# SWAPv0_1.net
KiCad netlist of a schematic drawn in EAGLE
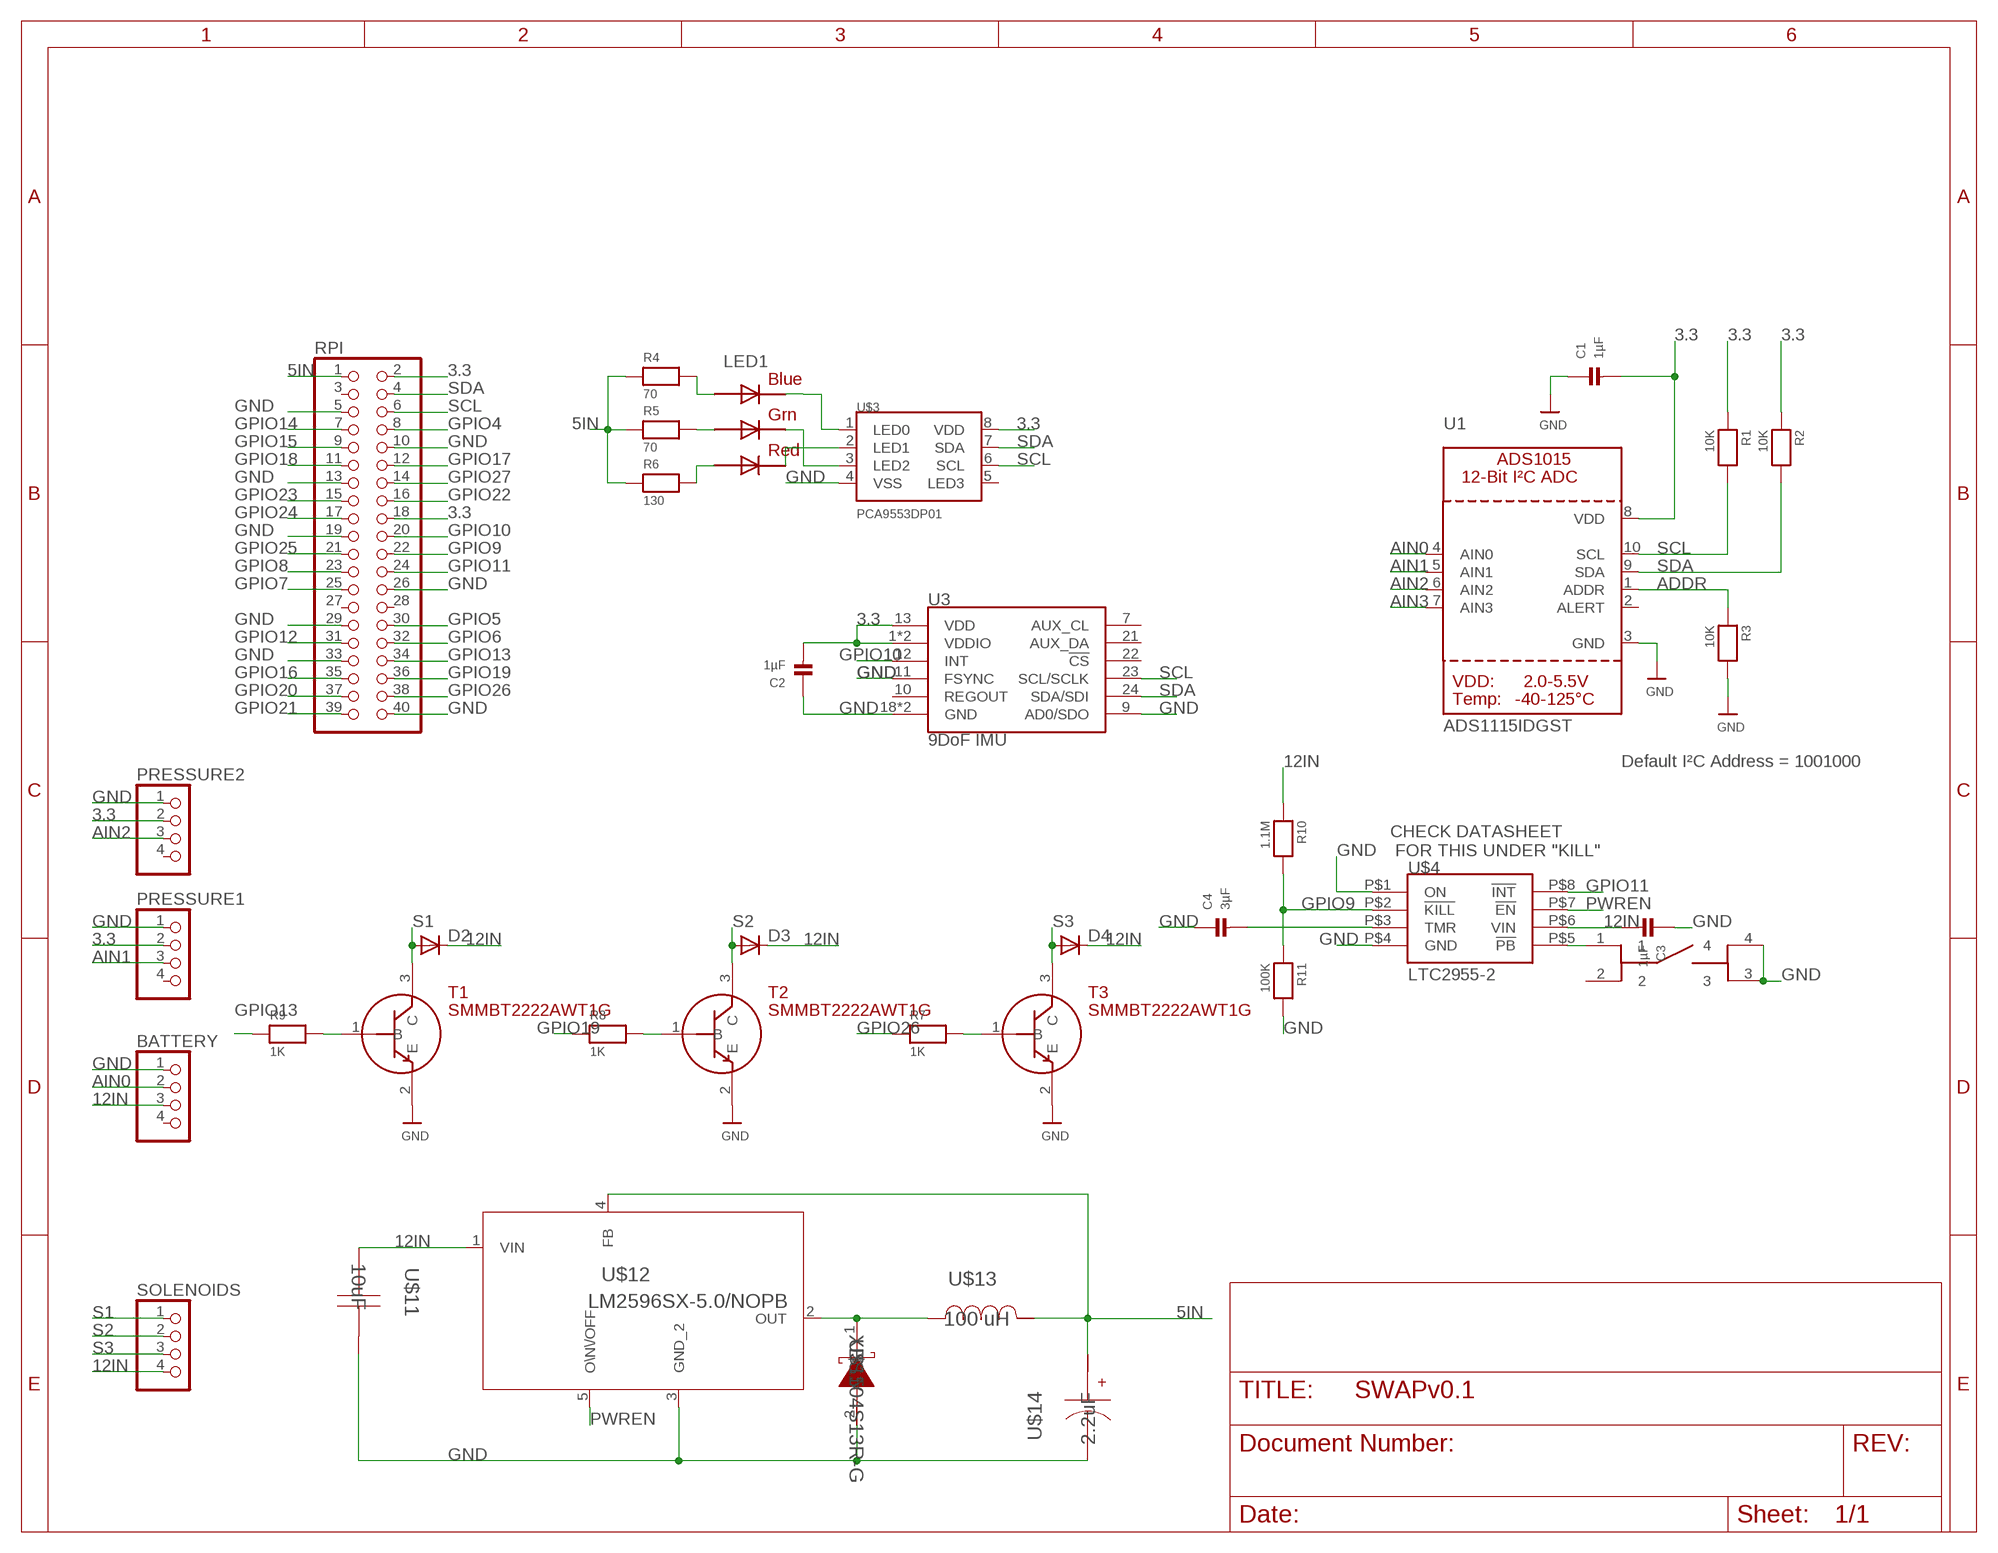
[diagram p0: schematic, sheet 1]

(export (version "E")
  (design (tool "Eeschema 10.0.6"))
  (components
    (comp (ref "BATTERY")
      (value "JST_4PIN")
      (footprint "eagle-import:JSTPH4")
      (libsource (lib "eagle-import") (part "JST_4PIN"))
    )
    (comp (ref "C1")
      (value "1µF")
      (footprint "eagle-import:1206")
      (libsource (lib "eagle-import") (part "CAP_CERAMIC1206"))
    )
    (comp (ref "C2")
      (value "1µF")
      (footprint "eagle-import:1206")
      (libsource (lib "eagle-import") (part "CAP_CERAMIC1206"))
    )
    (comp (ref "C3")
      (value "1µF")
      (footprint "eagle-import:1206")
      (libsource (lib "eagle-import") (part "CAP_CERAMIC1206"))
    )
    (comp (ref "C4")
      (value "3µF")
      (footprint "eagle-import:1206")
      (libsource (lib "eagle-import") (part "CAP_CERAMIC1206"))
    )
    (comp (ref "D2")
      (value "DIODE-DO214AA")
      (footprint "eagle-import:DO214AA")
      (libsource (lib "eagle-import") (part "DIODE-DO214AA"))
    )
    (comp (ref "D3")
      (value "DIODE-DO214AA")
      (footprint "eagle-import:DO214AA")
      (libsource (lib "eagle-import") (part "DIODE-DO214AA"))
    )
    (comp (ref "D4")
      (value "DIODE-DO214AA")
      (footprint "eagle-import:DO214AA")
      (libsource (lib "eagle-import") (part "DIODE-DO214AA"))
    )
    (comp (ref "LED1")
      (value "RGBLED5050")
      (footprint "eagle-import:RGBLED5050")
      (libsource (lib "eagle-import") (part "RGBLED5050"))
    )
    (comp (ref "PRESSURE1")
      (value "JST_4PIN")
      (footprint "eagle-import:JSTPH4")
      (libsource (lib "eagle-import") (part "JST_4PIN"))
    )
    (comp (ref "PRESSURE2")
      (value "JST_4PIN")
      (footprint "eagle-import:JSTPH4")
      (libsource (lib "eagle-import") (part "JST_4PIN"))
    )
    (comp (ref "R1")
      (value "10K")
      (footprint "eagle-import:2512")
      (libsource (lib "eagle-import") (part "RESISTOR2512"))
    )
    (comp (ref "R2")
      (value "10K")
      (footprint "eagle-import:2512")
      (libsource (lib "eagle-import") (part "RESISTOR2512"))
    )
    (comp (ref "R3")
      (value "10K")
      (footprint "eagle-import:2512")
      (libsource (lib "eagle-import") (part "RESISTOR2512"))
    )
    (comp (ref "R4")
      (value "70")
      (footprint "eagle-import:2512")
      (libsource (lib "eagle-import") (part "RESISTOR2512"))
    )
    (comp (ref "R5")
      (value "70")
      (footprint "eagle-import:2512")
      (libsource (lib "eagle-import") (part "RESISTOR2512"))
    )
    (comp (ref "R6")
      (value "130")
      (footprint "eagle-import:2512")
      (libsource (lib "eagle-import") (part "RESISTOR2512"))
    )
    (comp (ref "R7")
      (value "1K")
      (footprint "eagle-import:2512")
      (libsource (lib "eagle-import") (part "RESISTOR2512"))
    )
    (comp (ref "R8")
      (value "1K")
      (footprint "eagle-import:2512")
      (libsource (lib "eagle-import") (part "RESISTOR2512"))
    )
    (comp (ref "R9")
      (value "1K")
      (footprint "eagle-import:2512")
      (libsource (lib "eagle-import") (part "RESISTOR2512"))
    )
    (comp (ref "R10")
      (value "1.1M")
      (footprint "eagle-import:2512")
      (libsource (lib "eagle-import") (part "RESISTOR2512"))
    )
    (comp (ref "R11")
      (value "100K")
      (footprint "eagle-import:2512")
      (libsource (lib "eagle-import") (part "RESISTOR2512"))
    )
    (comp (ref "RPI")
      (value "PINHD-2X20")
      (footprint "eagle-import:2X20")
      (libsource (lib "eagle-import") (part "PINHD-2X20"))
    )
    (comp (ref "SOLENOIDS")
      (value "JST_4PIN")
      (footprint "eagle-import:JSTPH4")
      (libsource (lib "eagle-import") (part "JST_4PIN"))
    )
    (comp (ref "T1")
      (value "SMMBT2222AWT1G")
      (footprint "eagle-import:SOT323")
      (libsource (lib "eagle-import") (part "SMMBT2222AWT1G"))
    )
    (comp (ref "T2")
      (value "SMMBT2222AWT1G")
      (footprint "eagle-import:SOT323")
      (libsource (lib "eagle-import") (part "SMMBT2222AWT1G"))
    )
    (comp (ref "T3")
      (value "SMMBT2222AWT1G")
      (footprint "eagle-import:SOT323")
      (libsource (lib "eagle-import") (part "SMMBT2222AWT1G"))
    )
    (comp (ref "U$3")
      (value "PCA9553DP01")
      (footprint "eagle-import:TSSOP8")
      (libsource (lib "eagle-import") (part "PCA9553DP01"))
    )
    (comp (ref "U$4")
      (value "LTC2955-2")
      (footprint "eagle-import:TSOT23-8")
      (fields (field (name "SPICEPREFIX") "X"))
      (libsource (lib "eagle-import") (part "LTC2955-2"))
    )
    (comp (ref "U$10")
      (value "B3FS-1015")
      (footprint "eagle-import:B3FS")
      (libsource (lib "eagle-import") (part "B3FS-1015"))
    )
    (comp (ref "U$11")
      (value "10uF")
      (footprint "eagle-import:0805")
      (fields (field (name "MANUFACTURER_PART_NUMBER") "C2012X5R1V106K085AC"))
      (libsource (lib "eagle-import") (part "C2012X5R1V106K085AC"))
    )
    (comp (ref "U$12")
      (value "LM2596SX-5.0/NOPB")
      (footprint "eagle-import:TS5B")
      (fields (field (name "MANUFACTURER_PART_NUMBER") "LM2596SX5.0NOPB"))
      (libsource (lib "eagle-import") (part "LM2596SX-5.0/NOPB"))
    )
    (comp (ref "U$13")
      (value "100 uH")
      (footprint "eagle-import:MSS1246T")
      (fields (field (name "MANUFACTURER_PART_NUMBER") "MSS1246T104MLB"))
      (libsource (lib "eagle-import") (part "MSS1246T-104MLB"))
    )
    (comp (ref "U$14")
      (value "2.2uF")
      (footprint "eagle-import:3216-18")
      (fields (field (name "MANUFACTURER_PART_NUMBER") "TPSA225K035R1500"))
      (libsource (lib "eagle-import") (part "TPSA225K035R1500"))
    )
    (comp (ref "U$15")
      (value "XBS104S13R-G")
      (footprint "eagle-import:SOD-323")
      (fields (field (name "MANUFACTURER_PART_NUMBER") "XBS104S13RG"))
      (libsource (lib "eagle-import") (part "XBS104S13R-G"))
    )
    (comp (ref "U1")
      (value "ADS1115IDGST")
      (footprint "eagle-import:MSOP10")
      (libsource (lib "eagle-import") (part "ADC_ADS1015"))
    )
    (comp (ref "U3")
      (value "9DoF IMU")
      (footprint "eagle-import:QFN24-3X3")
      (libsource (lib "eagle-import") (part "MPU-9250"))
    )
  )
  (nets
    (net (code "1") (name "/3.3") (class "Default")
      (node (ref "C1") (pin "2") (pinfunction "P$2_2") (pintype "passive"))
      (node (ref "C2") (pin "2") (pinfunction "P$2_2") (pintype "passive"))
      (node (ref "PRESSURE1") (pin "2") (pinfunction "2_2") (pintype "passive"))
      (node (ref "PRESSURE2") (pin "2") (pinfunction "2_2") (pintype "passive"))
      (node (ref "R1") (pin "1") (pinfunction "1_1") (pintype "passive"))
      (node (ref "R2") (pin "1") (pinfunction "1_1") (pintype "passive"))
      (node (ref "RPI") (pin "18") (pinfunction "18_18") (pintype "passive"))
      (node (ref "RPI") (pin "2") (pinfunction "2_2") (pintype "passive"))
      (node (ref "U$3") (pin "8") (pinfunction "VDD_8") (pintype "power_in"))
      (node (ref "U1") (pin "8") (pinfunction "VDD_8") (pintype "bidirectional"))
      (node (ref "U3") (pin "1") (pinfunction "VDDIO_1") (pintype "bidirectional"))
      (node (ref "U3") (pin "13") (pinfunction "VDD_13") (pintype "bidirectional"))
      (node (ref "U3") (pin "8") (pinfunction "VDDIO_8") (pintype "bidirectional"))
    )
    (net (code "2") (name "/5IN") (class "Default")
      (node (ref "R4") (pin "1") (pinfunction "1_1") (pintype "passive"))
      (node (ref "R5") (pin "1") (pinfunction "1_1") (pintype "passive"))
      (node (ref "R6") (pin "1") (pinfunction "1_1") (pintype "passive"))
      (node (ref "RPI") (pin "1") (pinfunction "1_1") (pintype "passive"))
      (node (ref "U$12") (pin "4") (pinfunction "FB_4") (pintype "passive"))
      (node (ref "U$13") (pin "2") (pinfunction "2_2") (pintype "passive"))
      (node (ref "U$14") (pin "1") (pinfunction "+_1") (pintype "passive"))
    )
    (net (code "3") (name "/12IN") (class "Default")
      (node (ref "BATTERY") (pin "3") (pinfunction "3_3") (pintype "passive"))
      (node (ref "C3") (pin "2") (pinfunction "P$2_2") (pintype "passive"))
      (node (ref "D2") (pin "C") (pinfunction "C_C") (pintype "passive"))
      (node (ref "D3") (pin "C") (pinfunction "C_C") (pintype "passive"))
      (node (ref "D4") (pin "C") (pinfunction "C_C") (pintype "passive"))
      (node (ref "R10") (pin "1") (pinfunction "1_1") (pintype "passive"))
      (node (ref "SOLENOIDS") (pin "4") (pinfunction "4_4") (pintype "passive"))
      (node (ref "U$11") (pin "2") (pinfunction "2_2") (pintype "passive"))
      (node (ref "U$12") (pin "1") (pinfunction "VIN_1") (pintype "passive"))
      (node (ref "U$4") (pin "P$6") (pinfunction "VIN_P$6") (pintype "power_in"))
    )
    (net (code "4") (name "/ADDR") (class "Default")
      (node (ref "R3") (pin "1") (pinfunction "1_1") (pintype "passive"))
      (node (ref "U1") (pin "1") (pinfunction "ADDR_1") (pintype "bidirectional"))
    )
    (net (code "5") (name "/AIN0") (class "Default")
      (node (ref "BATTERY") (pin "2") (pinfunction "2_2") (pintype "passive"))
      (node (ref "U1") (pin "4") (pinfunction "AIN0_4") (pintype "bidirectional"))
    )
    (net (code "6") (name "/AIN1") (class "Default")
      (node (ref "PRESSURE1") (pin "3") (pinfunction "3_3") (pintype "passive"))
      (node (ref "U1") (pin "5") (pinfunction "AIN1_5") (pintype "bidirectional"))
    )
    (net (code "7") (name "/AIN2") (class "Default")
      (node (ref "PRESSURE2") (pin "3") (pinfunction "3_3") (pintype "passive"))
      (node (ref "U1") (pin "6") (pinfunction "AIN2_6") (pintype "bidirectional"))
    )
    (net (code "8") (name "/AIN3") (class "Default")
      (node (ref "U1") (pin "7") (pinfunction "AIN3_7") (pintype "bidirectional"))
    )
    (net (code "9") (name "/GPIO4") (class "Default")
      (node (ref "RPI") (pin "8") (pinfunction "8_8") (pintype "passive"))
    )
    (net (code "10") (name "/GPIO5") (class "Default")
      (node (ref "RPI") (pin "30") (pinfunction "30_30") (pintype "passive"))
    )
    (net (code "11") (name "/GPIO6") (class "Default")
      (node (ref "RPI") (pin "32") (pinfunction "32_32") (pintype "passive"))
    )
    (net (code "12") (name "/GPIO7") (class "Default")
      (node (ref "RPI") (pin "25") (pinfunction "25_25") (pintype "passive"))
    )
    (net (code "13") (name "/GPIO8") (class "Default")
      (node (ref "RPI") (pin "23") (pinfunction "23_23") (pintype "passive"))
    )
    (net (code "14") (name "/GPIO9") (class "Default")
      (node (ref "R10") (pin "2") (pinfunction "2_2") (pintype "passive"))
      (node (ref "R11") (pin "1") (pinfunction "1_1") (pintype "passive"))
      (node (ref "RPI") (pin "22") (pinfunction "22_22") (pintype "passive"))
      (node (ref "U$4") (pin "P$2") (pinfunction "~{KILL}_P$2") (pintype "bidirectional"))
    )
    (net (code "15") (name "/GPIO10") (class "Default")
      (node (ref "RPI") (pin "20") (pinfunction "20_20") (pintype "passive"))
      (node (ref "U3") (pin "12") (pinfunction "INT_12") (pintype "bidirectional"))
    )
    (net (code "16") (name "/GPIO11") (class "Default")
      (node (ref "RPI") (pin "24") (pinfunction "24_24") (pintype "passive"))
      (node (ref "U$4") (pin "P$8") (pinfunction "~{INT}_P$8") (pintype "output"))
    )
    (net (code "17") (name "/GPIO12") (class "Default")
      (node (ref "RPI") (pin "31") (pinfunction "31_31") (pintype "passive"))
    )
    (net (code "18") (name "/GPIO13") (class "Default")
      (node (ref "R9") (pin "1") (pinfunction "1_1") (pintype "passive"))
      (node (ref "RPI") (pin "34") (pinfunction "34_34") (pintype "passive"))
    )
    (net (code "19") (name "/GPIO14") (class "Default")
      (node (ref "RPI") (pin "7") (pinfunction "7_7") (pintype "passive"))
    )
    (net (code "20") (name "/GPIO15") (class "Default")
      (node (ref "RPI") (pin "9") (pinfunction "9_9") (pintype "passive"))
    )
    (net (code "21") (name "/GPIO16") (class "Default")
      (node (ref "RPI") (pin "35") (pinfunction "35_35") (pintype "passive"))
    )
    (net (code "22") (name "/GPIO17") (class "Default")
      (node (ref "RPI") (pin "12") (pinfunction "12_12") (pintype "passive"))
    )
    (net (code "23") (name "/GPIO18") (class "Default")
      (node (ref "RPI") (pin "11") (pinfunction "11_11") (pintype "passive"))
    )
    (net (code "24") (name "/GPIO19") (class "Default")
      (node (ref "R8") (pin "1") (pinfunction "1_1") (pintype "passive"))
      (node (ref "RPI") (pin "36") (pinfunction "36_36") (pintype "passive"))
    )
    (net (code "25") (name "/GPIO20") (class "Default")
      (node (ref "RPI") (pin "37") (pinfunction "37_37") (pintype "passive"))
    )
    (net (code "26") (name "/GPIO21") (class "Default")
      (node (ref "RPI") (pin "39") (pinfunction "39_39") (pintype "passive"))
    )
    (net (code "27") (name "/GPIO22") (class "Default")
      (node (ref "RPI") (pin "16") (pinfunction "16_16") (pintype "passive"))
    )
    (net (code "28") (name "/GPIO23") (class "Default")
      (node (ref "RPI") (pin "15") (pinfunction "15_15") (pintype "passive"))
    )
    (net (code "29") (name "/GPIO24") (class "Default")
      (node (ref "RPI") (pin "17") (pinfunction "17_17") (pintype "passive"))
    )
    (net (code "30") (name "/GPIO25") (class "Default")
      (node (ref "RPI") (pin "21") (pinfunction "21_21") (pintype "passive"))
    )
    (net (code "31") (name "/GPIO26") (class "Default")
      (node (ref "R7") (pin "1") (pinfunction "1_1") (pintype "passive"))
      (node (ref "RPI") (pin "38") (pinfunction "38_38") (pintype "passive"))
    )
    (net (code "32") (name "/GPIO27") (class "Default")
      (node (ref "RPI") (pin "14") (pinfunction "14_14") (pintype "passive"))
    )
    (net (code "33") (name "/PWREN") (class "Default")
      (node (ref "U$12") (pin "5") (pinfunction "O\\N\\/OFF_5") (pintype "passive"))
      (node (ref "U$4") (pin "P$7") (pinfunction "~{EN}_P$7") (pintype "output"))
    )
    (net (code "34") (name "/S1") (class "Default")
      (node (ref "D2") (pin "A") (pinfunction "A_A") (pintype "passive"))
      (node (ref "SOLENOIDS") (pin "1") (pinfunction "1_1") (pintype "passive"))
      (node (ref "T1") (pin "3") (pinfunction "C_3") (pintype "input"))
    )
    (net (code "35") (name "/S2") (class "Default")
      (node (ref "D3") (pin "A") (pinfunction "A_A") (pintype "passive"))
      (node (ref "SOLENOIDS") (pin "2") (pinfunction "2_2") (pintype "passive"))
      (node (ref "T2") (pin "3") (pinfunction "C_3") (pintype "input"))
    )
    (net (code "36") (name "/S3") (class "Default")
      (node (ref "D4") (pin "A") (pinfunction "A_A") (pintype "passive"))
      (node (ref "SOLENOIDS") (pin "3") (pinfunction "3_3") (pintype "passive"))
      (node (ref "T3") (pin "3") (pinfunction "C_3") (pintype "input"))
    )
    (net (code "37") (name "/SCL") (class "Default")
      (node (ref "R1") (pin "2") (pinfunction "2_2") (pintype "passive"))
      (node (ref "RPI") (pin "6") (pinfunction "6_6") (pintype "passive"))
      (node (ref "U$3") (pin "6") (pinfunction "SCL_6") (pintype "bidirectional"))
      (node (ref "U1") (pin "10") (pinfunction "SCL_10") (pintype "bidirectional"))
      (node (ref "U3") (pin "23") (pinfunction "SCL/SCLK_23") (pintype "bidirectional"))
    )
    (net (code "38") (name "/SDA") (class "Default")
      (node (ref "R2") (pin "2") (pinfunction "2_2") (pintype "passive"))
      (node (ref "RPI") (pin "4") (pinfunction "4_4") (pintype "passive"))
      (node (ref "U$3") (pin "7") (pinfunction "SDA_7") (pintype "bidirectional"))
      (node (ref "U1") (pin "9") (pinfunction "SDA_9") (pintype "bidirectional"))
      (node (ref "U3") (pin "24") (pinfunction "SDA/SDI_24") (pintype "bidirectional"))
    )
    (net (code "39") (name "GND") (class "Default")
      (node (ref "BATTERY") (pin "1") (pinfunction "1_1") (pintype "passive"))
      (node (ref "C1") (pin "1") (pinfunction "P$1_1") (pintype "passive"))
      (node (ref "C2") (pin "1") (pinfunction "P$1_1") (pintype "passive"))
      (node (ref "C3") (pin "1") (pinfunction "P$1_1") (pintype "passive"))
      (node (ref "C4") (pin "1") (pinfunction "P$1_1") (pintype "passive"))
      (node (ref "PRESSURE1") (pin "1") (pinfunction "1_1") (pintype "passive"))
      (node (ref "PRESSURE2") (pin "1") (pinfunction "1_1") (pintype "passive"))
      (node (ref "R11") (pin "2") (pinfunction "2_2") (pintype "passive"))
      (node (ref "R3") (pin "2") (pinfunction "2_2") (pintype "passive"))
      (node (ref "RPI") (pin "10") (pinfunction "10_10") (pintype "passive"))
      (node (ref "RPI") (pin "13") (pinfunction "13_13") (pintype "passive"))
      (node (ref "RPI") (pin "19") (pinfunction "19_19") (pintype "passive"))
      (node (ref "RPI") (pin "26") (pinfunction "26_26") (pintype "passive"))
      (node (ref "RPI") (pin "29") (pinfunction "29_29") (pintype "passive"))
      (node (ref "RPI") (pin "33") (pinfunction "33_33") (pintype "passive"))
      (node (ref "RPI") (pin "40") (pinfunction "40_40") (pintype "passive"))
      (node (ref "RPI") (pin "5") (pinfunction "5_5") (pintype "passive"))
      (node (ref "T1") (pin "2") (pinfunction "E_2") (pintype "output"))
      (node (ref "T2") (pin "2") (pinfunction "E_2") (pintype "output"))
      (node (ref "T3") (pin "2") (pinfunction "E_2") (pintype "output"))
      (node (ref "U$10") (pin "3") (pinfunction "3_3") (pintype "bidirectional"))
      (node (ref "U$10") (pin "4") (pinfunction "4_4") (pintype "bidirectional"))
      (node (ref "U$11") (pin "1") (pinfunction "1_1") (pintype "passive"))
      (node (ref "U$12") (pin "3") (pinfunction "GND_2_3") (pintype "passive"))
      (node (ref "U$14") (pin "2") (pinfunction "-_2") (pintype "passive"))
      (node (ref "U$15") (pin "2") (pinfunction "A_2") (pintype "passive"))
      (node (ref "U$3") (pin "4") (pinfunction "VSS_4") (pintype "power_in"))
      (node (ref "U$4") (pin "P$1") (pinfunction "ON_P$1") (pintype "bidirectional"))
      (node (ref "U$4") (pin "P$4") (pinfunction "GND_P$4") (pintype "power_in"))
      (node (ref "U1") (pin "3") (pinfunction "GND_3") (pintype "bidirectional"))
      (node (ref "U3") (pin "11") (pinfunction "FSYNC_11") (pintype "bidirectional"))
      (node (ref "U3") (pin "18") (pinfunction "GND_18") (pintype "bidirectional"))
      (node (ref "U3") (pin "20") (pinfunction "GND_20") (pintype "bidirectional"))
      (node (ref "U3") (pin "9") (pinfunction "AD0/SDO_9") (pintype "bidirectional"))
    )
    (net (code "40") (name "Net-(C4-P$2)") (class "Default")
      (node (ref "C4") (pin "2") (pinfunction "P$2_2") (pintype "passive"))
      (node (ref "U$4") (pin "P$3") (pinfunction "TMR_P$3") (pintype "bidirectional"))
    )
    (net (code "41") (name "Net-(LED1-BLUE_A)") (class "Default")
      (node (ref "LED1") (pin "3") (pinfunction "BLUE_A_3") (pintype "bidirectional"))
      (node (ref "R4") (pin "2") (pinfunction "2_2") (pintype "passive"))
    )
    (net (code "42") (name "Net-(LED1-BLUE_C)") (class "Default")
      (node (ref "LED1") (pin "4") (pinfunction "BLUE_C_4") (pintype "bidirectional"))
      (node (ref "U$3") (pin "1") (pinfunction "LED0_1") (pintype "output"))
    )
    (net (code "43") (name "Net-(LED1-GREEN_A)") (class "Default")
      (node (ref "LED1") (pin "1") (pinfunction "GREEN_A_1") (pintype "bidirectional"))
      (node (ref "R5") (pin "2") (pinfunction "2_2") (pintype "passive"))
    )
    (net (code "44") (name "Net-(LED1-GREEN_C)") (class "Default")
      (node (ref "LED1") (pin "6") (pinfunction "GREEN_C_6") (pintype "bidirectional"))
      (node (ref "U$3") (pin "3") (pinfunction "LED2_3") (pintype "output"))
    )
    (net (code "45") (name "Net-(LED1-RED_A)") (class "Default")
      (node (ref "LED1") (pin "2") (pinfunction "RED_A_2") (pintype "bidirectional"))
      (node (ref "R6") (pin "2") (pinfunction "2_2") (pintype "passive"))
    )
    (net (code "46") (name "Net-(LED1-RED_C)") (class "Default")
      (node (ref "LED1") (pin "5") (pinfunction "RED_C_5") (pintype "bidirectional"))
      (node (ref "U$3") (pin "2") (pinfunction "LED1_2") (pintype "output"))
    )
    (net (code "47") (name "Net-(T1-B)") (class "Default")
      (node (ref "R9") (pin "2") (pinfunction "2_2") (pintype "passive"))
      (node (ref "T1") (pin "1") (pinfunction "B_1") (pintype "input"))
    )
    (net (code "48") (name "Net-(T2-B)") (class "Default")
      (node (ref "R8") (pin "2") (pinfunction "2_2") (pintype "passive"))
      (node (ref "T2") (pin "1") (pinfunction "B_1") (pintype "input"))
    )
    (net (code "49") (name "Net-(T3-B)") (class "Default")
      (node (ref "R7") (pin "2") (pinfunction "2_2") (pintype "passive"))
      (node (ref "T3") (pin "1") (pinfunction "B_1") (pintype "input"))
    )
    (net (code "50") (name "Net-(U$4-~{PB})") (class "Default")
      (node (ref "U$10") (pin "1") (pinfunction "1_1") (pintype "bidirectional"))
      (node (ref "U$4") (pin "P$5") (pinfunction "~{PB}_P$5") (pintype "bidirectional"))
    )
    (net (code "51") (name "Net-(U$12-OUT)") (class "Default")
      (node (ref "U$12") (pin "2") (pinfunction "OUT_2") (pintype "passive"))
      (node (ref "U$13") (pin "1") (pinfunction "1_1") (pintype "passive"))
      (node (ref "U$15") (pin "1") (pinfunction "K_1") (pintype "passive"))
    )
    (net (code "52") (name "unconnected-(BATTERY-Pad4)") (class "Default")
      (node (ref "BATTERY") (pin "4") (pinfunction "4_4") (pintype "passive"))
    )
    (net (code "53") (name "unconnected-(PRESSURE1-Pad4)") (class "Default")
      (node (ref "PRESSURE1") (pin "4") (pinfunction "4_4") (pintype "passive"))
    )
    (net (code "54") (name "unconnected-(PRESSURE2-Pad4)") (class "Default")
      (node (ref "PRESSURE2") (pin "4") (pinfunction "4_4") (pintype "passive"))
    )
    (net (code "55") (name "unconnected-(RPI-Pad3)") (class "Default")
      (node (ref "RPI") (pin "3") (pinfunction "3_3") (pintype "passive"))
    )
    (net (code "56") (name "unconnected-(RPI-Pad27)") (class "Default")
      (node (ref "RPI") (pin "27") (pinfunction "27_27") (pintype "passive"))
    )
    (net (code "57") (name "unconnected-(RPI-Pad28)") (class "Default")
      (node (ref "RPI") (pin "28") (pinfunction "28_28") (pintype "passive"))
    )
    (net (code "58") (name "unconnected-(U$3-LED3-Pad5)") (class "Default")
      (node (ref "U$3") (pin "5") (pinfunction "LED3_5") (pintype "output"))
    )
    (net (code "59") (name "unconnected-(U$10-Pad2)") (class "Default")
      (node (ref "U$10") (pin "2") (pinfunction "2_2") (pintype "bidirectional"))
    )
    (net (code "60") (name "unconnected-(U1-ALERT-Pad2)") (class "Default")
      (node (ref "U1") (pin "2") (pinfunction "ALERT_2") (pintype "bidirectional"))
    )
    (net (code "61") (name "unconnected-(U3-AUX_CL-Pad7)") (class "Default")
      (node (ref "U3") (pin "7") (pinfunction "AUX_CL_7") (pintype "bidirectional"))
    )
    (net (code "62") (name "unconnected-(U3-AUX_DA-Pad21)") (class "Default")
      (node (ref "U3") (pin "21") (pinfunction "AUX_DA_21") (pintype "bidirectional"))
    )
    (net (code "63") (name "unconnected-(U3-REGOUT-Pad10)") (class "Default")
      (node (ref "U3") (pin "10") (pinfunction "REGOUT_10") (pintype "bidirectional"))
    )
    (net (code "64") (name "unconnected-(U3-~{CS}-Pad22)") (class "Default")
      (node (ref "U3") (pin "22") (pinfunction "~{CS}_22") (pintype "bidirectional"))
    )
  )
)
